# esp32_adapter_05.net
KiCad netlist of a schematic drawn in EAGLE
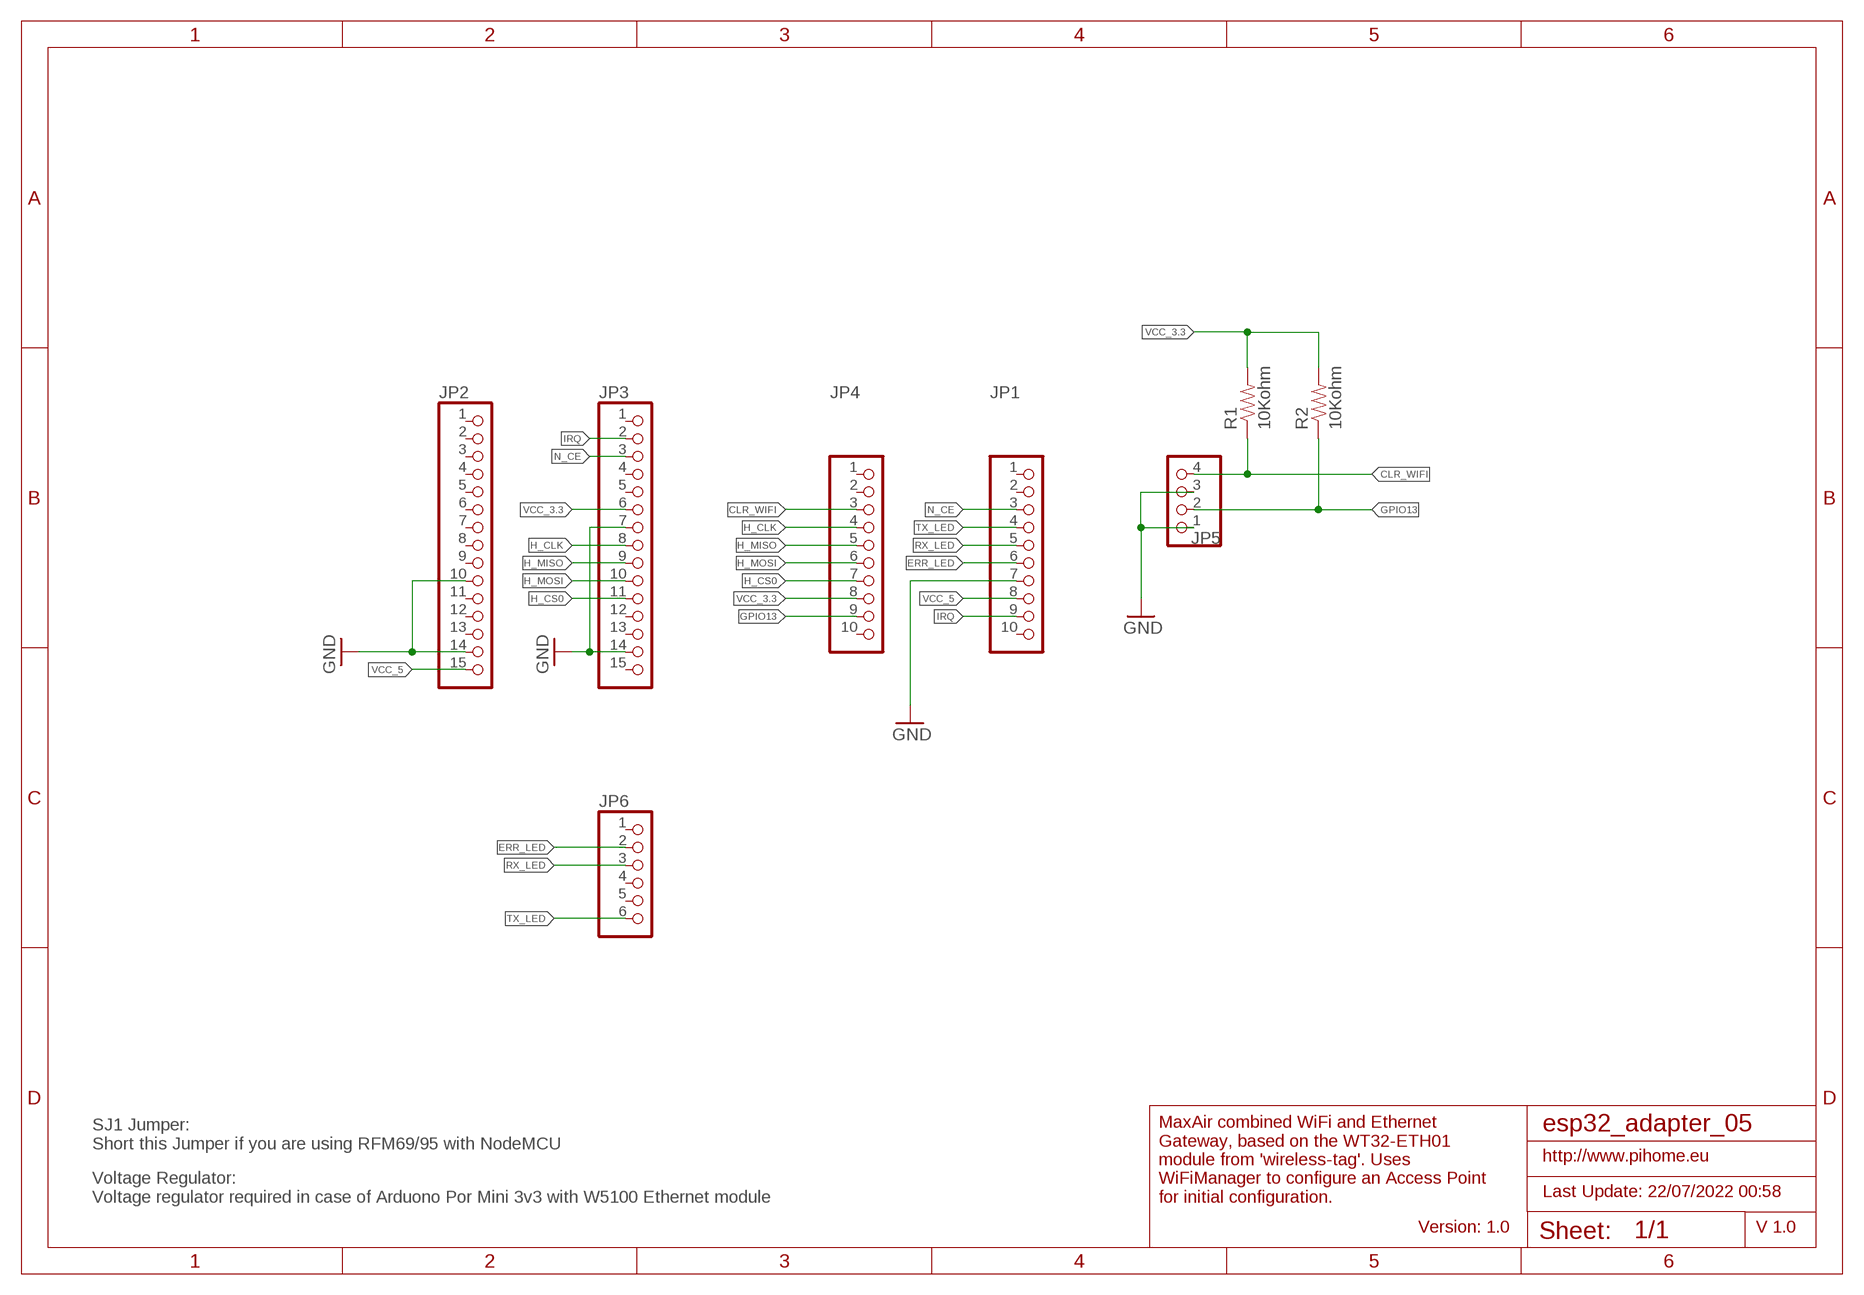
[diagram p0: schematic, sheet 1]

(export (version "E")
  (design (tool "Eeschema 10.0.6"))
  (components
    (comp (ref "JP1")
      (value "PINHD-1X10")
      (footprint "eagle-import:1X10-BIG")
      (libsource (lib "eagle-import") (part "PINHD-1X10"))
    )
    (comp (ref "JP2")
      (value "PINHD-1X15-CB")
      (footprint "eagle-import:1X15-CB")
      (libsource (lib "eagle-import") (part "PINHD-1X15-CB"))
    )
    (comp (ref "JP3")
      (value "PINHD-1X15-CB")
      (footprint "eagle-import:1X15-CB")
      (libsource (lib "eagle-import") (part "PINHD-1X15-CB"))
    )
    (comp (ref "JP4")
      (value "PINHD-1X10")
      (footprint "eagle-import:1X10-BIG")
      (libsource (lib "eagle-import") (part "PINHD-1X10"))
    )
    (comp (ref "JP5")
      (value "PINHD-1X4/90")
      (footprint "eagle-import:1X04_90")
      (libsource (lib "eagle-import") (part "PINHD-1X4/90"))
    )
    (comp (ref "JP6")
      (value "PINHD-1X6CLEAN")
      (footprint "eagle-import:1X06-CLEAN")
      (libsource (lib "eagle-import") (part "PINHD-1X6CLEAN"))
    )
    (comp (ref "R1")
      (value "10Kohm")
      (footprint "eagle-import:AXIAL-0.3")
      (libsource (lib "eagle-import") (part "RESISTORAXIAL-0.3"))
    )
    (comp (ref "R2")
      (value "10Kohm")
      (footprint "eagle-import:AXIAL-0.3")
      (libsource (lib "eagle-import") (part "RESISTORAXIAL-0.3"))
    )
  )
  (nets
    (net (code "1") (name "CLR_WIFI") (class "Default")
      (node (ref "JP4") (pin "3") (pinfunction "3_3") (pintype "passive"))
      (node (ref "JP5") (pin "4") (pinfunction "4_4") (pintype "passive"))
      (node (ref "R1") (pin "P$1") (pinfunction "1_P$1") (pintype "passive"))
    )
    (net (code "2") (name "ERR_LED") (class "Default")
      (node (ref "JP1") (pin "6") (pinfunction "6_6") (pintype "passive"))
      (node (ref "JP6") (pin "2") (pinfunction "2_2") (pintype "passive"))
    )
    (net (code "3") (name "GND") (class "Default")
      (node (ref "JP1") (pin "7") (pinfunction "7_7") (pintype "passive"))
      (node (ref "JP2") (pin "10") (pinfunction "10_10") (pintype "passive"))
      (node (ref "JP2") (pin "14") (pinfunction "14_14") (pintype "passive"))
      (node (ref "JP3") (pin "14") (pinfunction "14_14") (pintype "passive"))
      (node (ref "JP3") (pin "7") (pinfunction "7_7") (pintype "passive"))
      (node (ref "JP5") (pin "1") (pinfunction "1_1") (pintype "passive"))
      (node (ref "JP5") (pin "3") (pinfunction "3_3") (pintype "passive"))
    )
    (net (code "4") (name "GPIO13") (class "Default")
      (node (ref "JP4") (pin "9") (pinfunction "9_9") (pintype "passive"))
      (node (ref "JP5") (pin "2") (pinfunction "2_2") (pintype "passive"))
      (node (ref "R2") (pin "P$1") (pinfunction "1_P$1") (pintype "passive"))
    )
    (net (code "5") (name "H_CLK") (class "Default")
      (node (ref "JP3") (pin "8") (pinfunction "8_8") (pintype "passive"))
      (node (ref "JP4") (pin "4") (pinfunction "4_4") (pintype "passive"))
    )
    (net (code "6") (name "H_CS0") (class "Default")
      (node (ref "JP3") (pin "11") (pinfunction "11_11") (pintype "passive"))
      (node (ref "JP4") (pin "7") (pinfunction "7_7") (pintype "passive"))
    )
    (net (code "7") (name "H_MISO") (class "Default")
      (node (ref "JP3") (pin "9") (pinfunction "9_9") (pintype "passive"))
      (node (ref "JP4") (pin "5") (pinfunction "5_5") (pintype "passive"))
    )
    (net (code "8") (name "H_MOSI") (class "Default")
      (node (ref "JP3") (pin "10") (pinfunction "10_10") (pintype "passive"))
      (node (ref "JP4") (pin "6") (pinfunction "6_6") (pintype "passive"))
    )
    (net (code "9") (name "IRQ") (class "Default")
      (node (ref "JP1") (pin "9") (pinfunction "9_9") (pintype "passive"))
      (node (ref "JP3") (pin "2") (pinfunction "2_2") (pintype "passive"))
    )
    (net (code "10") (name "N_CE") (class "Default")
      (node (ref "JP1") (pin "3") (pinfunction "3_3") (pintype "passive"))
      (node (ref "JP3") (pin "3") (pinfunction "3_3") (pintype "passive"))
    )
    (net (code "11") (name "RX_LED") (class "Default")
      (node (ref "JP1") (pin "5") (pinfunction "5_5") (pintype "passive"))
      (node (ref "JP6") (pin "3") (pinfunction "3_3") (pintype "passive"))
    )
    (net (code "12") (name "TX_LED") (class "Default")
      (node (ref "JP1") (pin "4") (pinfunction "4_4") (pintype "passive"))
      (node (ref "JP6") (pin "6") (pinfunction "6_6") (pintype "passive"))
    )
    (net (code "13") (name "VCC_3.3") (class "Default")
      (node (ref "JP3") (pin "6") (pinfunction "6_6") (pintype "passive"))
      (node (ref "JP4") (pin "8") (pinfunction "8_8") (pintype "passive"))
      (node (ref "R1") (pin "P$2") (pinfunction "2_P$2") (pintype "passive"))
      (node (ref "R2") (pin "P$2") (pinfunction "2_P$2") (pintype "passive"))
    )
    (net (code "14") (name "VCC_5") (class "Default")
      (node (ref "JP1") (pin "8") (pinfunction "8_8") (pintype "passive"))
      (node (ref "JP2") (pin "15") (pinfunction "15_15") (pintype "passive"))
    )
    (net (code "15") (name "unconnected-(JP1-Pad1)") (class "Default")
      (node (ref "JP1") (pin "1") (pinfunction "1_1") (pintype "passive"))
    )
    (net (code "16") (name "unconnected-(JP1-Pad2)") (class "Default")
      (node (ref "JP1") (pin "2") (pinfunction "2_2") (pintype "passive"))
    )
    (net (code "17") (name "unconnected-(JP1-Pad10)") (class "Default")
      (node (ref "JP1") (pin "10") (pinfunction "10_10") (pintype "passive"))
    )
    (net (code "18") (name "unconnected-(JP2-Pad1)") (class "Default")
      (node (ref "JP2") (pin "1") (pinfunction "1_1") (pintype "passive"))
    )
    (net (code "19") (name "unconnected-(JP2-Pad2)") (class "Default")
      (node (ref "JP2") (pin "2") (pinfunction "2_2") (pintype "passive"))
    )
    (net (code "20") (name "unconnected-(JP2-Pad3)") (class "Default")
      (node (ref "JP2") (pin "3") (pinfunction "3_3") (pintype "passive"))
    )
    (net (code "21") (name "unconnected-(JP2-Pad4)") (class "Default")
      (node (ref "JP2") (pin "4") (pinfunction "4_4") (pintype "passive"))
    )
    (net (code "22") (name "unconnected-(JP2-Pad5)") (class "Default")
      (node (ref "JP2") (pin "5") (pinfunction "5_5") (pintype "passive"))
    )
    (net (code "23") (name "unconnected-(JP2-Pad6)") (class "Default")
      (node (ref "JP2") (pin "6") (pinfunction "6_6") (pintype "passive"))
    )
    (net (code "24") (name "unconnected-(JP2-Pad7)") (class "Default")
      (node (ref "JP2") (pin "7") (pinfunction "7_7") (pintype "passive"))
    )
    (net (code "25") (name "unconnected-(JP2-Pad8)") (class "Default")
      (node (ref "JP2") (pin "8") (pinfunction "8_8") (pintype "passive"))
    )
    (net (code "26") (name "unconnected-(JP2-Pad9)") (class "Default")
      (node (ref "JP2") (pin "9") (pinfunction "9_9") (pintype "passive"))
    )
    (net (code "27") (name "unconnected-(JP2-Pad11)") (class "Default")
      (node (ref "JP2") (pin "11") (pinfunction "11_11") (pintype "passive"))
    )
    (net (code "28") (name "unconnected-(JP2-Pad12)") (class "Default")
      (node (ref "JP2") (pin "12") (pinfunction "12_12") (pintype "passive"))
    )
    (net (code "29") (name "unconnected-(JP2-Pad13)") (class "Default")
      (node (ref "JP2") (pin "13") (pinfunction "13_13") (pintype "passive"))
    )
    (net (code "30") (name "unconnected-(JP3-Pad1)") (class "Default")
      (node (ref "JP3") (pin "1") (pinfunction "1_1") (pintype "passive"))
    )
    (net (code "31") (name "unconnected-(JP3-Pad4)") (class "Default")
      (node (ref "JP3") (pin "4") (pinfunction "4_4") (pintype "passive"))
    )
    (net (code "32") (name "unconnected-(JP3-Pad5)") (class "Default")
      (node (ref "JP3") (pin "5") (pinfunction "5_5") (pintype "passive"))
    )
    (net (code "33") (name "unconnected-(JP3-Pad12)") (class "Default")
      (node (ref "JP3") (pin "12") (pinfunction "12_12") (pintype "passive"))
    )
    (net (code "34") (name "unconnected-(JP3-Pad13)") (class "Default")
      (node (ref "JP3") (pin "13") (pinfunction "13_13") (pintype "passive"))
    )
    (net (code "35") (name "unconnected-(JP3-Pad15)") (class "Default")
      (node (ref "JP3") (pin "15") (pinfunction "15_15") (pintype "passive"))
    )
    (net (code "36") (name "unconnected-(JP4-Pad1)") (class "Default")
      (node (ref "JP4") (pin "1") (pinfunction "1_1") (pintype "passive"))
    )
    (net (code "37") (name "unconnected-(JP4-Pad2)") (class "Default")
      (node (ref "JP4") (pin "2") (pinfunction "2_2") (pintype "passive"))
    )
    (net (code "38") (name "unconnected-(JP4-Pad10)") (class "Default")
      (node (ref "JP4") (pin "10") (pinfunction "10_10") (pintype "passive"))
    )
    (net (code "39") (name "unconnected-(JP6-Pad1)") (class "Default")
      (node (ref "JP6") (pin "1") (pinfunction "1_1") (pintype "passive"))
    )
    (net (code "40") (name "unconnected-(JP6-Pad4)") (class "Default")
      (node (ref "JP6") (pin "4") (pinfunction "4_4") (pintype "passive"))
    )
    (net (code "41") (name "unconnected-(JP6-Pad5)") (class "Default")
      (node (ref "JP6") (pin "5") (pinfunction "5_5") (pintype "passive"))
    )
  )
)
